# PedestrianController.net
KiCad netlist of a schematic drawn in EAGLE
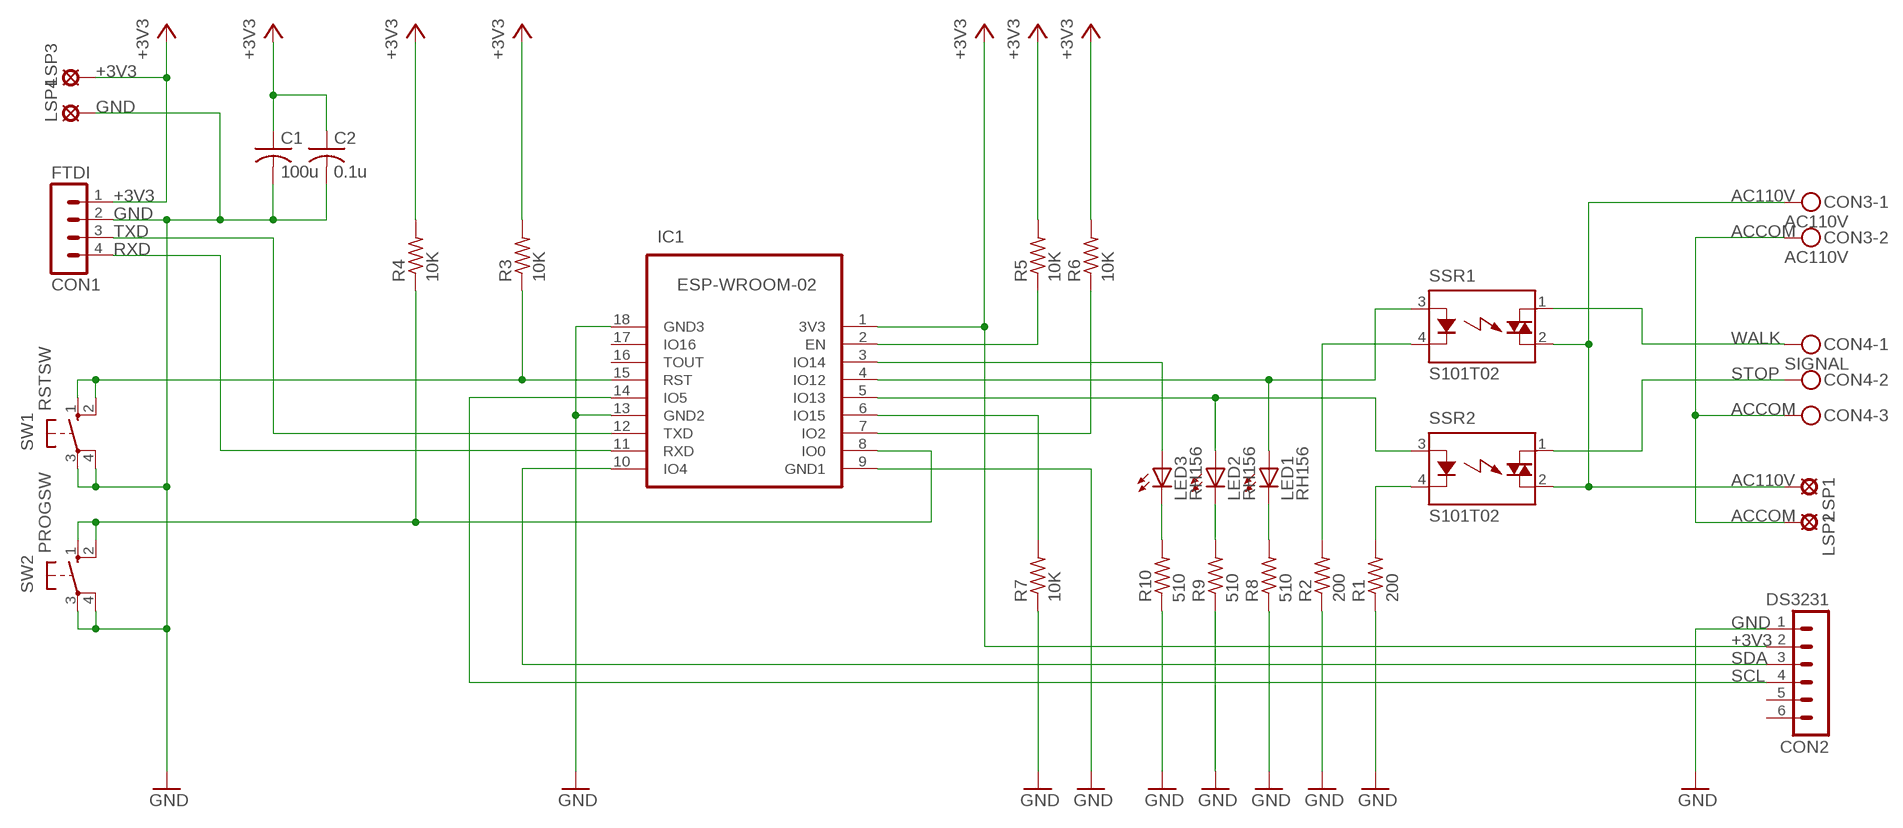
[diagram p0: schematic, sheet 1]

(export (version "E")
  (design (tool "Eeschema 10.0.6"))
  (components
    (comp (ref "C1")
      (value "100u")
      (footprint "eagle-import:C050-024X044")
      (libsource (lib "eagle-import") (part "C-US050-024X044"))
    )
    (comp (ref "C2")
      (value "0.1u")
      (footprint "eagle-import:C050-024X044")
      (libsource (lib "eagle-import") (part "C-US050-024X044"))
    )
    (comp (ref "CON1")
      (value "FTDI")
      (footprint "eagle-import:MA04-1")
      (libsource (lib "eagle-import") (part "MA04-1"))
    )
    (comp (ref "CON2")
      (value "DS3231")
      (footprint "eagle-import:MA06-1")
      (libsource (lib "eagle-import") (part "MA06-1"))
    )
    (comp (ref "CON3")
      (value "AC110V")
      (footprint "eagle-import:MKDSN1,5_2-5,08")
      (libsource (lib "eagle-import") (part "MKDSN1,5/2-5,08"))
    )
    (comp (ref "CON4")
      (value "SIGNAL")
      (footprint "eagle-import:MKDSN1,5_3-5,08")
      (libsource (lib "eagle-import") (part "MKDSN1,5/3-5,08"))
    )
    (comp (ref "IC1")
      (value "ESP-WROOM-02")
      (footprint "eagle-import:FRONT-FACE")
      (libsource (lib "eagle-import") (part "ESP-WROOM-02FRONT-FACE"))
    )
    (comp (ref "LED1")
      (value "RH156")
      (footprint "eagle-import:LED3MM")
      (fields (field (name "MF") "VISHAY SEMICONDUCTOR"))
      (libsource (lib "eagle-import") (part "TLLR4400"))
    )
    (comp (ref "LED2")
      (value "RH156")
      (footprint "eagle-import:LED3MM")
      (fields (field (name "MF") "VISHAY SEMICONDUCTOR"))
      (libsource (lib "eagle-import") (part "TLLR4400"))
    )
    (comp (ref "LED3")
      (value "RH156")
      (footprint "eagle-import:LED3MM")
      (fields (field (name "MF") "VISHAY SEMICONDUCTOR"))
      (libsource (lib "eagle-import") (part "TLLR4400"))
    )
    (comp (ref "LSP1")
      (value "LSP10")
      (footprint "eagle-import:LSP10")
      (libsource (lib "eagle-import") (part "LSP10"))
    )
    (comp (ref "LSP2")
      (value "LSP10")
      (footprint "eagle-import:LSP10")
      (libsource (lib "eagle-import") (part "LSP10"))
    )
    (comp (ref "LSP3")
      (value "LSP10")
      (footprint "eagle-import:LSP10")
      (libsource (lib "eagle-import") (part "LSP10"))
    )
    (comp (ref "LSP4")
      (value "LSP10")
      (footprint "eagle-import:LSP10")
      (libsource (lib "eagle-import") (part "LSP10"))
    )
    (comp (ref "R1")
      (value "200")
      (footprint "eagle-import:0204_7")
      (libsource (lib "eagle-import") (part "R-US_0204/7"))
    )
    (comp (ref "R2")
      (value "200")
      (footprint "eagle-import:0204_7")
      (libsource (lib "eagle-import") (part "R-US_0204/7"))
    )
    (comp (ref "R3")
      (value "10K")
      (footprint "eagle-import:0204_7")
      (libsource (lib "eagle-import") (part "R-US_0204/7"))
    )
    (comp (ref "R4")
      (value "10K")
      (footprint "eagle-import:0204_7")
      (libsource (lib "eagle-import") (part "R-US_0204/7"))
    )
    (comp (ref "R5")
      (value "10K")
      (footprint "eagle-import:0204_7")
      (libsource (lib "eagle-import") (part "R-US_0204/7"))
    )
    (comp (ref "R6")
      (value "10K")
      (footprint "eagle-import:0204_7")
      (libsource (lib "eagle-import") (part "R-US_0204/7"))
    )
    (comp (ref "R7")
      (value "10K")
      (footprint "eagle-import:0204_7")
      (libsource (lib "eagle-import") (part "R-US_0204/7"))
    )
    (comp (ref "R8")
      (value "510")
      (footprint "eagle-import:0204_7")
      (libsource (lib "eagle-import") (part "R-US_0204/7"))
    )
    (comp (ref "R9")
      (value "510")
      (footprint "eagle-import:0204_7")
      (libsource (lib "eagle-import") (part "R-US_0204/7"))
    )
    (comp (ref "R10")
      (value "510")
      (footprint "eagle-import:0204_7")
      (fields (field (name "SPICEPREFIX") "R"))
      (libsource (lib "eagle-import") (part "R-US_0204/7"))
    )
    (comp (ref "SSR1")
      (value "S101T02")
      (footprint "eagle-import:S102T0X")
      (libsource (lib "eagle-import") (part "S?101T02"))
    )
    (comp (ref "SSR2")
      (value "S101T02")
      (footprint "eagle-import:S102T0X")
      (libsource (lib "eagle-import") (part "S?101T02"))
    )
    (comp (ref "SW1")
      (value "RSTSW")
      (footprint "eagle-import:B3F-10XX")
      (fields (field (name "MPN") "B3F-1000"))
      (libsource (lib "eagle-import") (part "10-XX"))
    )
    (comp (ref "SW2")
      (value "PROGSW")
      (footprint "eagle-import:B3F-10XX")
      (fields (field (name "MPN") "B3F-1000"))
      (libsource (lib "eagle-import") (part "10-XX"))
    )
  )
  (nets
    (net (code "1") (name "+3V3") (class "Default")
      (node (ref "C1") (pin "1") (pinfunction "1_1") (pintype "passive"))
      (node (ref "C2") (pin "1") (pinfunction "1_1") (pintype "passive"))
      (node (ref "CON1") (pin "1") (pinfunction "1_1") (pintype "passive"))
      (node (ref "CON2") (pin "2") (pinfunction "2_2") (pintype "passive"))
      (node (ref "IC1") (pin "1") (pinfunction "3V3_1") (pintype "power_in"))
      (node (ref "LSP3") (pin "MP") (pinfunction "MP_MP") (pintype "passive"))
      (node (ref "R3") (pin "2") (pinfunction "2_2") (pintype "passive"))
      (node (ref "R4") (pin "2") (pinfunction "2_2") (pintype "passive"))
      (node (ref "R5") (pin "2") (pinfunction "2_2") (pintype "passive"))
      (node (ref "R6") (pin "2") (pinfunction "2_2") (pintype "passive"))
    )
    (net (code "2") (name "/AC110V") (class "Default")
      (node (ref "CON3") (pin "1") (pinfunction "KL_1") (pintype "passive"))
      (node (ref "LSP1") (pin "MP") (pinfunction "MP_MP") (pintype "passive"))
      (node (ref "SSR1") (pin "2") (pinfunction "DS2_2") (pintype "passive"))
      (node (ref "SSR2") (pin "2") (pinfunction "DS2_2") (pintype "passive"))
    )
    (net (code "3") (name "/ACCOM") (class "Default")
      (node (ref "CON3") (pin "2") (pinfunction "KL_2") (pintype "passive"))
      (node (ref "CON4") (pin "3") (pinfunction "KL_3") (pintype "passive"))
      (node (ref "LSP2") (pin "MP") (pinfunction "MP_MP") (pintype "passive"))
    )
    (net (code "4") (name "/RXD") (class "Default")
      (node (ref "CON1") (pin "4") (pinfunction "4_4") (pintype "passive"))
      (node (ref "IC1") (pin "11") (pinfunction "RXD_11") (pintype "bidirectional"))
    )
    (net (code "5") (name "/SCL") (class "Default")
      (node (ref "CON2") (pin "4") (pinfunction "4_4") (pintype "passive"))
      (node (ref "IC1") (pin "14") (pinfunction "IO5_14") (pintype "open_collector"))
    )
    (net (code "6") (name "/SDA") (class "Default")
      (node (ref "CON2") (pin "3") (pinfunction "3_3") (pintype "passive"))
      (node (ref "IC1") (pin "10") (pinfunction "IO4_10") (pintype "bidirectional"))
    )
    (net (code "7") (name "/STOP") (class "Default")
      (node (ref "CON4") (pin "2") (pinfunction "KL_2") (pintype "passive"))
      (node (ref "SSR2") (pin "1") (pinfunction "DS1_1") (pintype "passive"))
    )
    (net (code "8") (name "/TXD") (class "Default")
      (node (ref "CON1") (pin "3") (pinfunction "3_3") (pintype "passive"))
      (node (ref "IC1") (pin "12") (pinfunction "TXD_12") (pintype "bidirectional"))
    )
    (net (code "9") (name "/WALK") (class "Default")
      (node (ref "CON4") (pin "1") (pinfunction "KL_1") (pintype "passive"))
      (node (ref "SSR1") (pin "1") (pinfunction "DS1_1") (pintype "passive"))
    )
    (net (code "10") (name "GND") (class "Default")
      (node (ref "C1") (pin "2") (pinfunction "2_2") (pintype "passive"))
      (node (ref "C2") (pin "2") (pinfunction "2_2") (pintype "passive"))
      (node (ref "CON1") (pin "2") (pinfunction "2_2") (pintype "passive"))
      (node (ref "CON2") (pin "1") (pinfunction "1_1") (pintype "passive"))
      (node (ref "IC1") (pin "13") (pinfunction "GND2_13") (pintype "power_in"))
      (node (ref "IC1") (pin "18") (pinfunction "GND3_18") (pintype "power_in"))
      (node (ref "IC1") (pin "9") (pinfunction "GND1_9") (pintype "power_in"))
      (node (ref "LSP4") (pin "MP") (pinfunction "MP_MP") (pintype "passive"))
      (node (ref "R1") (pin "1") (pinfunction "1_1") (pintype "passive"))
      (node (ref "R10") (pin "1") (pinfunction "1_1") (pintype "passive"))
      (node (ref "R2") (pin "1") (pinfunction "1_1") (pintype "passive"))
      (node (ref "R7") (pin "1") (pinfunction "1_1") (pintype "passive"))
      (node (ref "R8") (pin "1") (pinfunction "1_1") (pintype "passive"))
      (node (ref "R9") (pin "1") (pinfunction "1_1") (pintype "passive"))
      (node (ref "SW1") (pin "3") (pinfunction "P_3") (pintype "passive"))
      (node (ref "SW1") (pin "4") (pinfunction "P1_4") (pintype "passive"))
      (node (ref "SW2") (pin "3") (pinfunction "P_3") (pintype "passive"))
      (node (ref "SW2") (pin "4") (pinfunction "P1_4") (pintype "passive"))
    )
    (net (code "11") (name "Net-(IC1-EN)") (class "Default")
      (node (ref "IC1") (pin "2") (pinfunction "EN_2") (pintype "bidirectional"))
      (node (ref "R5") (pin "1") (pinfunction "1_1") (pintype "passive"))
    )
    (net (code "12") (name "Net-(IC1-IO0)") (class "Default")
      (node (ref "IC1") (pin "8") (pinfunction "IO0_8") (pintype "bidirectional"))
      (node (ref "R4") (pin "1") (pinfunction "1_1") (pintype "passive"))
      (node (ref "SW2") (pin "1") (pinfunction "S_1") (pintype "passive"))
      (node (ref "SW2") (pin "2") (pinfunction "S1_2") (pintype "passive"))
    )
    (net (code "13") (name "Net-(IC1-IO2)") (class "Default")
      (node (ref "IC1") (pin "7") (pinfunction "IO2_7") (pintype "bidirectional"))
      (node (ref "R6") (pin "1") (pinfunction "1_1") (pintype "passive"))
    )
    (net (code "14") (name "Net-(IC1-IO12)") (class "Default")
      (node (ref "IC1") (pin "4") (pinfunction "IO12_4") (pintype "bidirectional"))
      (node (ref "LED1") (pin "A") (pinfunction "A_A") (pintype "passive"))
      (node (ref "SSR1") (pin "3") (pinfunction "A_3") (pintype "passive"))
    )
    (net (code "15") (name "Net-(IC1-IO13)") (class "Default")
      (node (ref "IC1") (pin "5") (pinfunction "IO13_5") (pintype "bidirectional"))
      (node (ref "LED2") (pin "A") (pinfunction "A_A") (pintype "passive"))
      (node (ref "SSR2") (pin "3") (pinfunction "A_3") (pintype "passive"))
    )
    (net (code "16") (name "Net-(IC1-IO14)") (class "Default")
      (node (ref "IC1") (pin "3") (pinfunction "IO14_3") (pintype "bidirectional"))
      (node (ref "LED3") (pin "A") (pinfunction "A_A") (pintype "passive"))
    )
    (net (code "17") (name "Net-(IC1-IO15)") (class "Default")
      (node (ref "IC1") (pin "6") (pinfunction "IO15_6") (pintype "bidirectional"))
      (node (ref "R7") (pin "2") (pinfunction "2_2") (pintype "passive"))
    )
    (net (code "18") (name "Net-(IC1-RST)") (class "Default")
      (node (ref "IC1") (pin "15") (pinfunction "RST_15") (pintype "bidirectional"))
      (node (ref "R3") (pin "1") (pinfunction "1_1") (pintype "passive"))
      (node (ref "SW1") (pin "1") (pinfunction "S_1") (pintype "passive"))
      (node (ref "SW1") (pin "2") (pinfunction "S1_2") (pintype "passive"))
    )
    (net (code "19") (name "Net-(LED1-C)") (class "Default")
      (node (ref "LED1") (pin "K") (pinfunction "C_K") (pintype "passive"))
      (node (ref "R8") (pin "2") (pinfunction "2_2") (pintype "passive"))
    )
    (net (code "20") (name "Net-(LED2-C)") (class "Default")
      (node (ref "LED2") (pin "K") (pinfunction "C_K") (pintype "passive"))
      (node (ref "R9") (pin "2") (pinfunction "2_2") (pintype "passive"))
    )
    (net (code "21") (name "Net-(LED3-C)") (class "Default")
      (node (ref "LED3") (pin "K") (pinfunction "C_K") (pintype "passive"))
      (node (ref "R10") (pin "2") (pinfunction "2_2") (pintype "passive"))
    )
    (net (code "22") (name "Net-(SSR1-K)") (class "Default")
      (node (ref "R2") (pin "2") (pinfunction "2_2") (pintype "passive"))
      (node (ref "SSR1") (pin "4") (pinfunction "K_4") (pintype "passive"))
    )
    (net (code "23") (name "Net-(SSR2-K)") (class "Default")
      (node (ref "R1") (pin "2") (pinfunction "2_2") (pintype "passive"))
      (node (ref "SSR2") (pin "4") (pinfunction "K_4") (pintype "passive"))
    )
    (net (code "24") (name "unconnected-(CON2-Pad5)") (class "Default")
      (node (ref "CON2") (pin "5") (pinfunction "5_5") (pintype "passive"))
    )
    (net (code "25") (name "unconnected-(CON2-Pad6)") (class "Default")
      (node (ref "CON2") (pin "6") (pinfunction "6_6") (pintype "passive"))
    )
    (net (code "26") (name "unconnected-(IC1-IO16-Pad17)") (class "Default")
      (node (ref "IC1") (pin "17") (pinfunction "IO16_17") (pintype "bidirectional"))
    )
    (net (code "27") (name "unconnected-(IC1-TOUT-Pad16)") (class "Default")
      (node (ref "IC1") (pin "16") (pinfunction "TOUT_16") (pintype "bidirectional"))
    )
  )
)
